# Connectors.net
KiCad netlist of a schematic drawn in Altium Designer
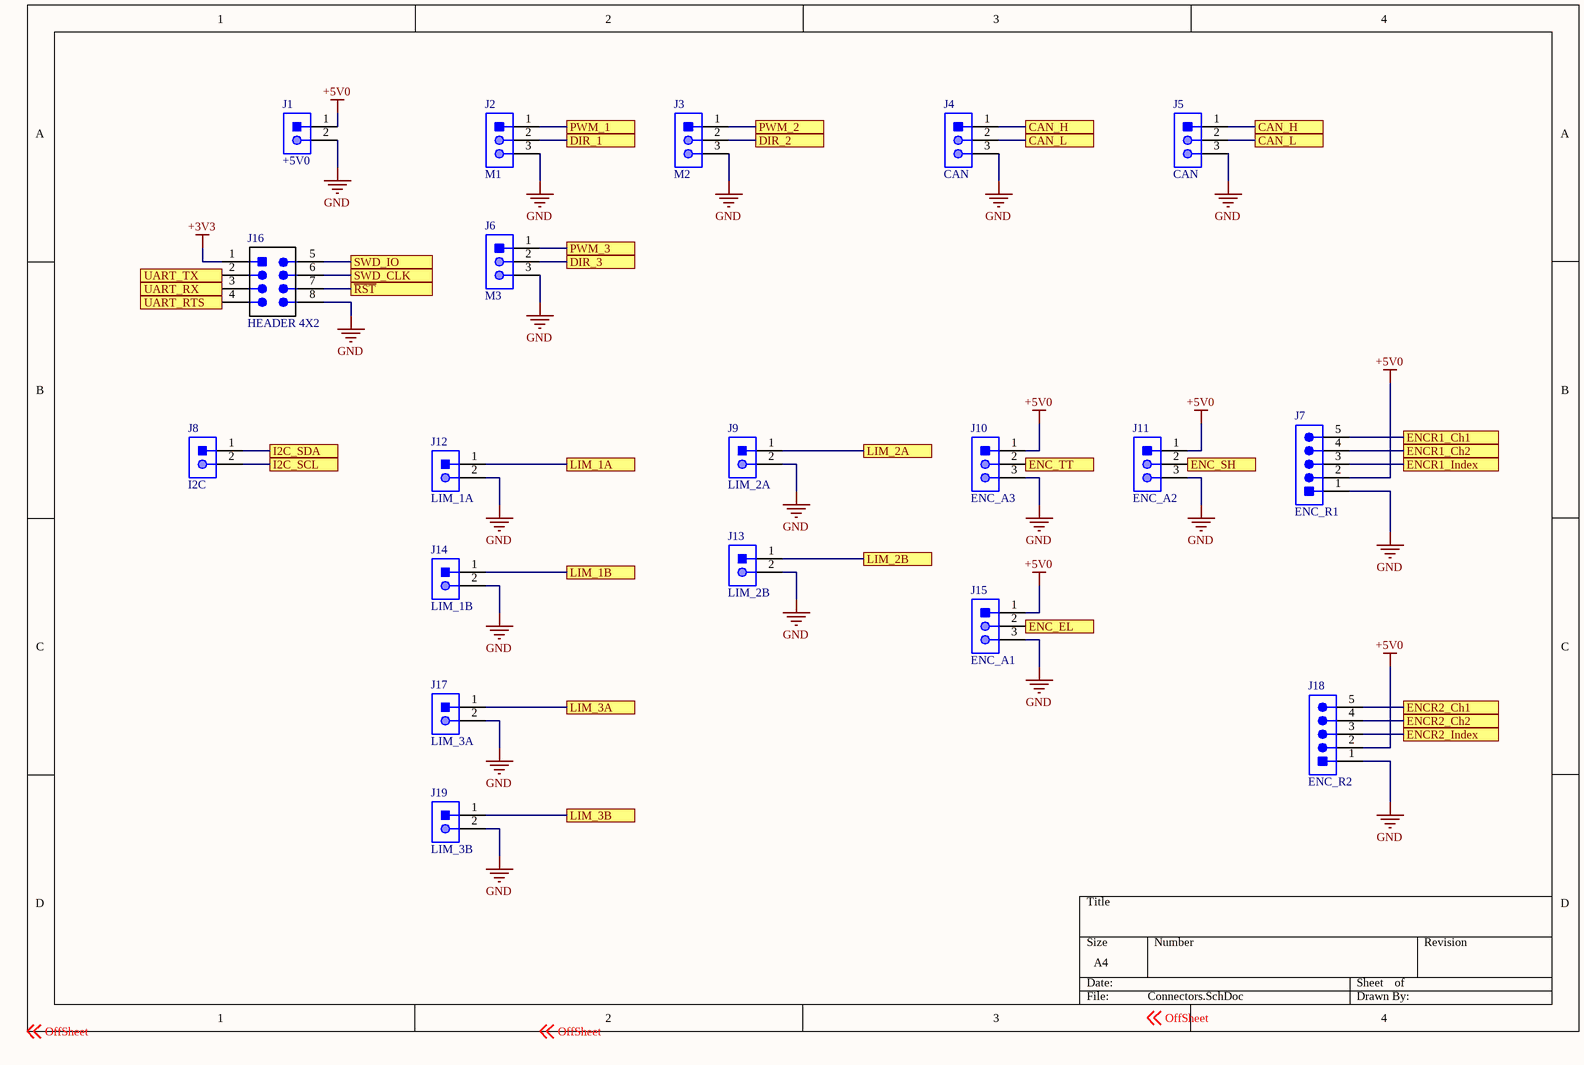
[diagram p0: Connectors.SchDoc]

(export (version "E")
  (design (tool "Eeschema 10.0.6"))
  (components
    (comp (ref "J1")
      (value "+5V0")
      (footprint "JST-B2B-SM4-TB")
      (description "CONN HEADER PH TOP 2POS 2MM SMD")
      (fields (field (name "MANUFACTURER") "JST") (field (name "MPN") "B2B-PH-SM4-TB"))
      (libsource (lib "UWRT_Schematic_Library_2019") (part "CON_2M_PH_TOP_SMT"))
    )
    (comp (ref "J2")
      (value "M1")
      (footprint "JST-B3B-SM4-TB")
      (description "CONN HEADER PH TOP 3POS 2MM SMD")
      (fields (field (name "MANUFACTURER") "JST") (field (name "MPN") "B3B-PH-SM4-TB(LF)(SN)"))
      (libsource (lib "UWRT_Schematic_Library_2019") (part "CON_3M_PH_TOP_SMT"))
    )
    (comp (ref "J3")
      (value "M2")
      (footprint "JST-B3B-SM4-TB")
      (description "CONN HEADER PH TOP 3POS 2MM SMD")
      (fields (field (name "MANUFACTURER") "JST") (field (name "MPN") "B3B-PH-SM4-TB(LF)(SN)"))
      (libsource (lib "UWRT_Schematic_Library_2019") (part "CON_3M_PH_TOP_SMT"))
    )
    (comp (ref "J4")
      (value "CAN")
      (footprint "JST-B3B-SM4-TB")
      (description "CONN HEADER PH TOP 3POS 2MM SMD")
      (fields (field (name "MANUFACTURER") "JST") (field (name "MPN") "B3B-PH-SM4-TB(LF)(SN)"))
      (libsource (lib "UWRT_Schematic_Library_2019") (part "CON_3M_PH_TOP_SMT"))
    )
    (comp (ref "J5")
      (value "CAN")
      (footprint "JST-B3B-SM4-TB")
      (description "CONN HEADER PH TOP 3POS 2MM SMD")
      (fields (field (name "MANUFACTURER") "JST") (field (name "MPN") "B3B-PH-SM4-TB(LF)(SN)"))
      (libsource (lib "UWRT_Schematic_Library_2019") (part "CON_3M_PH_TOP_SMT"))
    )
    (comp (ref "J6")
      (value "M3")
      (footprint "JST-B3B-SM4-TB")
      (description "CONN HEADER PH TOP 3POS 2MM SMD")
      (fields (field (name "MANUFACTURER") "JST") (field (name "MPN") "B3B-PH-SM4-TB(LF)(SN)"))
      (libsource (lib "UWRT_Schematic_Library_2019") (part "CON_3M_PH_TOP_SMT"))
    )
    (comp (ref "J7")
      (value "ENC_R1")
      (footprint "JST-B5B-SM4-TB")
      (description "CONN HEADER PH TOP 5POS 2MM SMD")
      (fields (field (name "MANUFACTURER") "JST") (field (name "MPN") "B5B-PH-SM4-TB(LF)(SN)"))
      (libsource (lib "UWRT_Schematic_Library_2019") (part "CON_5M_PH_TOP_SMT"))
    )
    (comp (ref "J8")
      (value "I2C")
      (footprint "JST-B2B-SM4-TB")
      (description "CONN HEADER PH TOP 2POS 2MM SMD")
      (fields (field (name "MANUFACTURER") "JST") (field (name "MPN") "B2B-PH-SM4-TB"))
      (libsource (lib "UWRT_Schematic_Library_2019") (part "CON_2M_PH_TOP_SMT"))
    )
    (comp (ref "J9")
      (value "LIM_2A")
      (footprint "JST-B2B-SM4-TB")
      (description "CONN HEADER PH TOP 2POS 2MM SMD")
      (fields (field (name "MANUFACTURER") "JST") (field (name "MPN") "B2B-PH-SM4-TB"))
      (libsource (lib "UWRT_Schematic_Library_2019") (part "CON_2M_PH_TOP_SMT"))
    )
    (comp (ref "J10")
      (value "ENC_A3")
      (footprint "JST-B3B-SM4-TB")
      (description "CONN HEADER PH TOP 3POS 2MM SMD")
      (fields (field (name "MANUFACTURER") "JST") (field (name "MPN") "B3B-PH-SM4-TB(LF)(SN)"))
      (libsource (lib "UWRT_Schematic_Library_2019") (part "CON_3M_PH_TOP_SMT"))
    )
    (comp (ref "J11")
      (value "ENC_A2")
      (footprint "JST-B3B-SM4-TB")
      (description "CONN HEADER PH TOP 3POS 2MM SMD")
      (fields (field (name "MANUFACTURER") "JST") (field (name "MPN") "B3B-PH-SM4-TB(LF)(SN)"))
      (libsource (lib "UWRT_Schematic_Library_2019") (part "CON_3M_PH_TOP_SMT"))
    )
    (comp (ref "J12")
      (value "LIM_1A")
      (footprint "JST-B2B-SM4-TB")
      (description "CONN HEADER PH TOP 2POS 2MM SMD")
      (fields (field (name "MANUFACTURER") "JST") (field (name "MPN") "B2B-PH-SM4-TB"))
      (libsource (lib "UWRT_Schematic_Library_2019") (part "CON_2M_PH_TOP_SMT"))
    )
    (comp (ref "J13")
      (value "LIM_2B")
      (footprint "JST-B2B-SM4-TB")
      (description "CONN HEADER PH TOP 2POS 2MM SMD")
      (fields (field (name "MANUFACTURER") "JST") (field (name "MPN") "B2B-PH-SM4-TB"))
      (libsource (lib "UWRT_Schematic_Library_2019") (part "CON_2M_PH_TOP_SMT"))
    )
    (comp (ref "J14")
      (value "LIM_1B")
      (footprint "JST-B2B-SM4-TB")
      (description "CONN HEADER PH TOP 2POS 2MM SMD")
      (fields (field (name "MANUFACTURER") "JST") (field (name "MPN") "B2B-PH-SM4-TB"))
      (libsource (lib "UWRT_Schematic_Library_2019") (part "CON_2M_PH_TOP_SMT"))
    )
    (comp (ref "J15")
      (value "ENC_A1")
      (footprint "JST-B3B-SM4-TB")
      (description "CONN HEADER PH TOP 3POS 2MM SMD")
      (fields (field (name "MANUFACTURER") "JST") (field (name "MPN") "B3B-PH-SM4-TB(LF)(SN)"))
      (libsource (lib "UWRT_Schematic_Library_2019") (part "CON_3M_PH_TOP_SMT"))
    )
    (comp (ref "J16")
      (value "HEADER 4X2")
      (footprint "UWRT_Footprint_Library_2019:HEADER_2X4")
      (description "Header, 4-Pin Dual row")
      (fields (field (name "MPN") "GRPB042VWVN-RC") (field (name "DIGIKEY PART NUMBER") "S9015E-04-ND"))
      (libsource (lib "UWRT_Schematic_Library_2019") (part "HEADER 4X2"))
    )
    (comp (ref "J17")
      (value "LIM_3A")
      (footprint "JST-B2B-SM4-TB")
      (description "CONN HEADER PH TOP 2POS 2MM SMD")
      (fields (field (name "MANUFACTURER") "JST") (field (name "MPN") "B2B-PH-SM4-TB"))
      (libsource (lib "UWRT_Schematic_Library_2019") (part "CON_2M_PH_TOP_SMT"))
    )
    (comp (ref "J18")
      (value "ENC_R2")
      (footprint "JST-B5B-SM4-TB")
      (description "CONN HEADER PH TOP 5POS 2MM SMD")
      (fields (field (name "MANUFACTURER") "JST") (field (name "MPN") "B5B-PH-SM4-TB(LF)(SN)"))
      (libsource (lib "UWRT_Schematic_Library_2019") (part "CON_5M_PH_TOP_SMT"))
    )
    (comp (ref "J19")
      (value "LIM_3B")
      (footprint "JST-B2B-SM4-TB")
      (description "CONN HEADER PH TOP 2POS 2MM SMD")
      (fields (field (name "MANUFACTURER") "JST") (field (name "MPN") "B2B-PH-SM4-TB"))
      (libsource (lib "UWRT_Schematic_Library_2019") (part "CON_2M_PH_TOP_SMT"))
    )
  )
  (nets
    (net (code "1") (name "+3V3") (class "Default")
      (node (ref "J16") (pin "1") (pinfunction "VCC_1") (pintype "passive"))
    )
    (net (code "2") (name "+5V0") (class "Default")
      (node (ref "J1") (pin "1") (pinfunction "1_1") (pintype "passive"))
      (node (ref "J10") (pin "1") (pinfunction "1_1") (pintype "passive"))
      (node (ref "J11") (pin "1") (pinfunction "1_1") (pintype "passive"))
      (node (ref "J15") (pin "1") (pinfunction "1_1") (pintype "passive"))
      (node (ref "J18") (pin "2") (pinfunction "2_2") (pintype "passive"))
      (node (ref "J7") (pin "2") (pinfunction "2_2") (pintype "passive"))
    )
    (net (code "3") (name "/CAN_H") (class "Default")
      (node (ref "J4") (pin "1") (pinfunction "1_1") (pintype "passive"))
      (node (ref "J5") (pin "1") (pinfunction "1_1") (pintype "passive"))
    )
    (net (code "4") (name "/CAN_L") (class "Default")
      (node (ref "J4") (pin "2") (pinfunction "2_2") (pintype "passive"))
      (node (ref "J5") (pin "2") (pinfunction "2_2") (pintype "passive"))
    )
    (net (code "5") (name "/DIR_1") (class "Default")
      (node (ref "J2") (pin "2") (pinfunction "2_2") (pintype "passive"))
    )
    (net (code "6") (name "/DIR_2") (class "Default")
      (node (ref "J3") (pin "2") (pinfunction "2_2") (pintype "passive"))
    )
    (net (code "7") (name "/DIR_3") (class "Default")
      (node (ref "J6") (pin "2") (pinfunction "2_2") (pintype "passive"))
    )
    (net (code "8") (name "/ENCR1_Ch1") (class "Default")
      (node (ref "J7") (pin "5") (pinfunction "5_5") (pintype "passive"))
    )
    (net (code "9") (name "/ENCR1_Ch2") (class "Default")
      (node (ref "J7") (pin "4") (pinfunction "4_4") (pintype "passive"))
    )
    (net (code "10") (name "/ENCR1_Index") (class "Default")
      (node (ref "J7") (pin "3") (pinfunction "3_3") (pintype "passive"))
    )
    (net (code "11") (name "/ENCR2_Ch1") (class "Default")
      (node (ref "J18") (pin "5") (pinfunction "5_5") (pintype "passive"))
    )
    (net (code "12") (name "/ENCR2_Ch2") (class "Default")
      (node (ref "J18") (pin "4") (pinfunction "4_4") (pintype "passive"))
    )
    (net (code "13") (name "/ENCR2_Index") (class "Default")
      (node (ref "J18") (pin "3") (pinfunction "3_3") (pintype "passive"))
    )
    (net (code "14") (name "/ENC_EL") (class "Default")
      (node (ref "J15") (pin "2") (pinfunction "2_2") (pintype "passive"))
    )
    (net (code "15") (name "/ENC_SH") (class "Default")
      (node (ref "J11") (pin "2") (pinfunction "2_2") (pintype "passive"))
    )
    (net (code "16") (name "/ENC_TT") (class "Default")
      (node (ref "J10") (pin "2") (pinfunction "2_2") (pintype "passive"))
    )
    (net (code "17") (name "/I2C_SCL") (class "Default")
      (node (ref "J8") (pin "2") (pinfunction "2_2") (pintype "passive"))
    )
    (net (code "18") (name "/I2C_SDA") (class "Default")
      (node (ref "J8") (pin "1") (pinfunction "1_1") (pintype "passive"))
    )
    (net (code "19") (name "/LIM_1A") (class "Default")
      (node (ref "J12") (pin "1") (pinfunction "1_1") (pintype "passive"))
    )
    (net (code "20") (name "/LIM_1B") (class "Default")
      (node (ref "J14") (pin "1") (pinfunction "1_1") (pintype "passive"))
    )
    (net (code "21") (name "/LIM_2A") (class "Default")
      (node (ref "J9") (pin "1") (pinfunction "1_1") (pintype "passive"))
    )
    (net (code "22") (name "/LIM_2B") (class "Default")
      (node (ref "J13") (pin "1") (pinfunction "1_1") (pintype "passive"))
    )
    (net (code "23") (name "/LIM_3A") (class "Default")
      (node (ref "J17") (pin "1") (pinfunction "1_1") (pintype "passive"))
    )
    (net (code "24") (name "/LIM_3B") (class "Default")
      (node (ref "J19") (pin "1") (pinfunction "1_1") (pintype "passive"))
    )
    (net (code "25") (name "/PWM_1") (class "Default")
      (node (ref "J2") (pin "1") (pinfunction "1_1") (pintype "passive"))
    )
    (net (code "26") (name "/PWM_2") (class "Default")
      (node (ref "J3") (pin "1") (pinfunction "1_1") (pintype "passive"))
    )
    (net (code "27") (name "/PWM_3") (class "Default")
      (node (ref "J6") (pin "1") (pinfunction "1_1") (pintype "passive"))
    )
    (net (code "28") (name "/SWD_CLK") (class "Default")
      (node (ref "J16") (pin "6") (pinfunction "2_6") (pintype "passive"))
    )
    (net (code "29") (name "/SWD_IO") (class "Default")
      (node (ref "J16") (pin "5") (pinfunction "GND_5") (pintype "passive"))
    )
    (net (code "30") (name "/UART_RTS") (class "Default")
      (node (ref "J16") (pin "4") (pinfunction "4_4") (pintype "passive"))
    )
    (net (code "31") (name "/UART_RX") (class "Default")
      (node (ref "J16") (pin "3") (pinfunction "3_3") (pintype "passive"))
    )
    (net (code "32") (name "/UART_TX") (class "Default")
      (node (ref "J16") (pin "2") (pinfunction "2_2") (pintype "passive"))
    )
    (net (code "33") (name "/~{RST}") (class "Default")
      (node (ref "J16") (pin "7") (pinfunction "3_7") (pintype "passive"))
    )
    (net (code "34") (name "GND") (class "Default")
      (node (ref "J1") (pin "2") (pinfunction "2_2") (pintype "passive"))
      (node (ref "J10") (pin "3") (pinfunction "3_3") (pintype "passive"))
      (node (ref "J11") (pin "3") (pinfunction "3_3") (pintype "passive"))
      (node (ref "J12") (pin "2") (pinfunction "2_2") (pintype "passive"))
      (node (ref "J13") (pin "2") (pinfunction "2_2") (pintype "passive"))
      (node (ref "J14") (pin "2") (pinfunction "2_2") (pintype "passive"))
      (node (ref "J15") (pin "3") (pinfunction "3_3") (pintype "passive"))
      (node (ref "J16") (pin "8") (pinfunction "4_8") (pintype "passive"))
      (node (ref "J17") (pin "2") (pinfunction "2_2") (pintype "passive"))
      (node (ref "J18") (pin "1") (pinfunction "1_1") (pintype "passive"))
      (node (ref "J19") (pin "2") (pinfunction "2_2") (pintype "passive"))
      (node (ref "J2") (pin "3") (pinfunction "3_3") (pintype "passive"))
      (node (ref "J3") (pin "3") (pinfunction "3_3") (pintype "passive"))
      (node (ref "J4") (pin "3") (pinfunction "3_3") (pintype "passive"))
      (node (ref "J5") (pin "3") (pinfunction "3_3") (pintype "passive"))
      (node (ref "J6") (pin "3") (pinfunction "3_3") (pintype "passive"))
      (node (ref "J7") (pin "1") (pinfunction "1_1") (pintype "passive"))
      (node (ref "J9") (pin "2") (pinfunction "2_2") (pintype "passive"))
    )
  )
)
